# MB1297_MCU1.net
KiCad netlist of a schematic drawn in Altium Designer
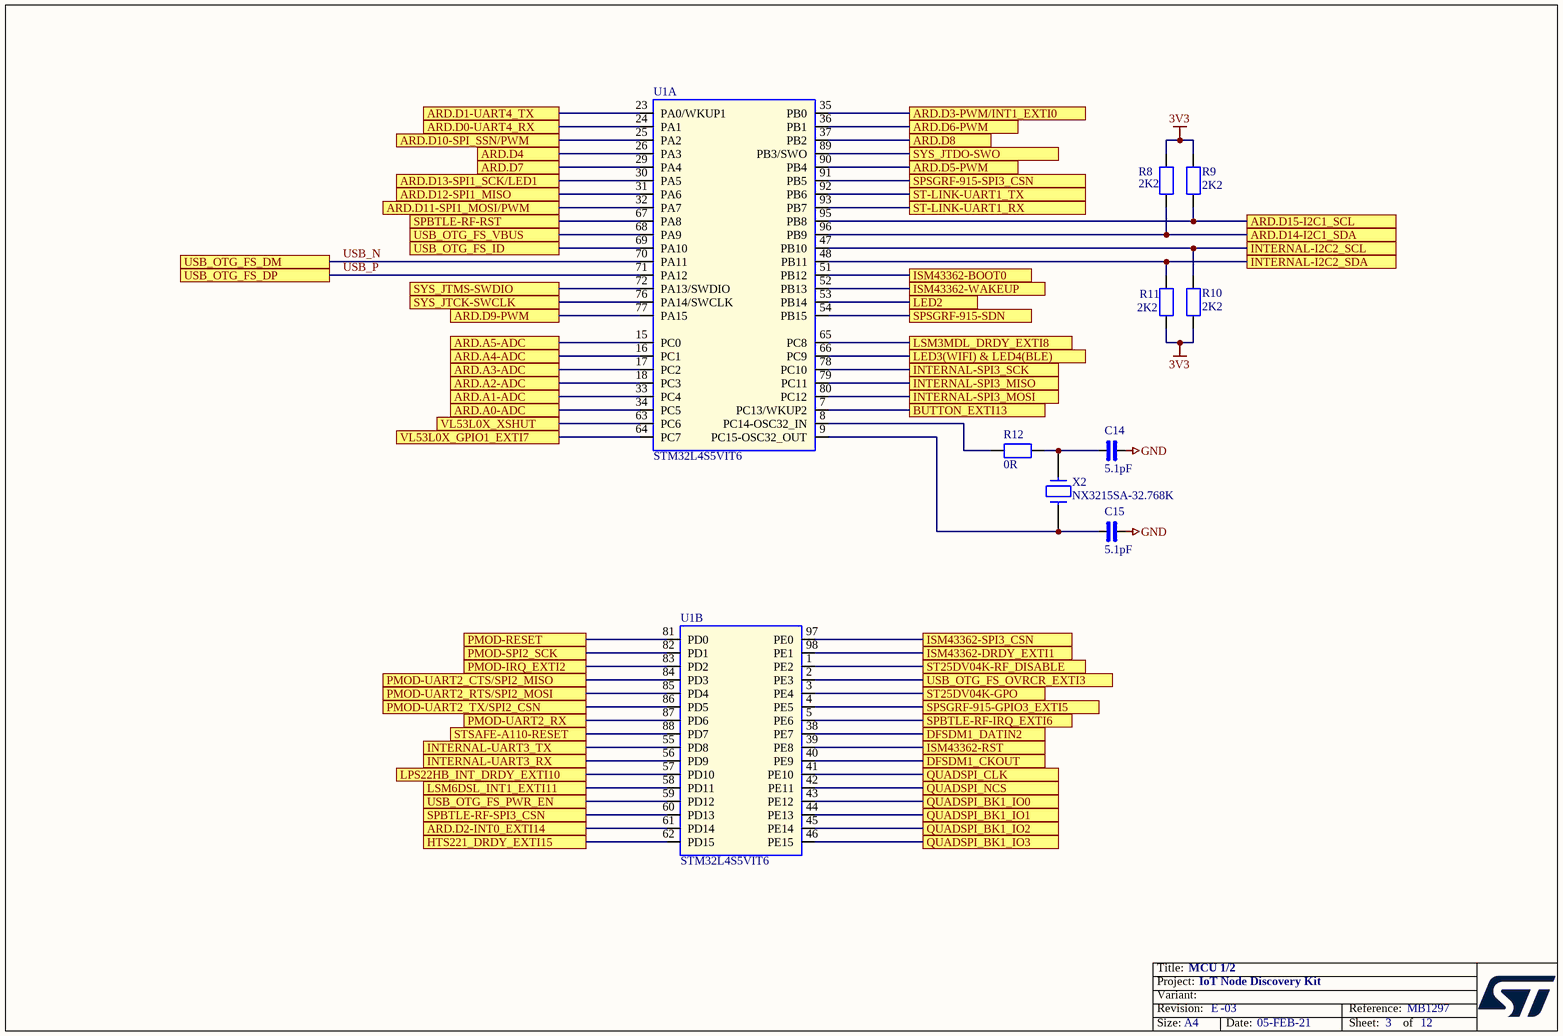
[diagram p0: MB1297_MCU1.SchDoc]

(export (version "E")
  (design (tool "Eeschema 10.0.6"))
  (components
    (comp (ref "C14")
      (value "5.1pF")
      (footprint "0402")
      (description "Capacitor_not polarized")
      (libsource (lib "ST_Lib3D") (part "CAP_NPOL"))
    )
    (comp (ref "C15")
      (value "5.1pF")
      (footprint "0402")
      (description "Capacitor_not polarized")
      (libsource (lib "ST_Lib3D") (part "CAP_NPOL"))
    )
    (comp (ref "R8")
      (value "2K2")
      (footprint "0402")
      (description "Resistor")
      (libsource (lib "ST_Lib3D") (part "RES"))
    )
    (comp (ref "R9")
      (value "2K2")
      (footprint "0402")
      (description "Resistor")
      (libsource (lib "ST_Lib3D") (part "RES"))
    )
    (comp (ref "R10")
      (value "2K2")
      (footprint "0402")
      (description "Resistor")
      (libsource (lib "ST_Lib3D") (part "RES"))
    )
    (comp (ref "R11")
      (value "2K2")
      (footprint "0402")
      (description "Resistor")
      (libsource (lib "ST_Lib3D") (part "RES"))
    )
    (comp (ref "R12")
      (value "0R")
      (footprint "0402")
      (description "Resistor")
      (libsource (lib "ST_Lib3D") (part "RES"))
    )
    (comp (ref "U1")
      (value "STM32L4S5VIT6")
      (footprint "ST_Lib3D:LQFP100 14x14x1.6")
      (description "STM32L475VGTx")
      (libsource (lib "ST_Lib3D") (part "STM32L475VGTx"))
    )
    (comp (ref "X2")
      (value "NX3215SA-32.768K")
      (footprint "CRY_NX3215SA_2P")
      (description "Crystal 32.768kHz, 6pF, -+20PPM, R=50K, SMD")
      (libsource (lib "MCD_TEMP_PCH") (part "XTAL_32K_NX3215SA"))
    )
  )
  (nets
    (net (code "1") (name "/ARD.A0-ADC") (class "Default")
      (node (ref "U1") (pin "34") (pinfunction "PC5_34") (pintype "passive"))
    )
    (net (code "2") (name "/ARD.A1-ADC") (class "Default")
      (node (ref "U1") (pin "33") (pinfunction "PC4_33") (pintype "passive"))
    )
    (net (code "3") (name "/ARD.A2-ADC") (class "Default")
      (node (ref "U1") (pin "18") (pinfunction "PC3_18") (pintype "passive"))
    )
    (net (code "4") (name "/ARD.A3-ADC") (class "Default")
      (node (ref "U1") (pin "17") (pinfunction "PC2_17") (pintype "passive"))
    )
    (net (code "5") (name "/ARD.A4-ADC") (class "Default")
      (node (ref "U1") (pin "16") (pinfunction "PC1_16") (pintype "passive"))
    )
    (net (code "6") (name "/ARD.A5-ADC") (class "Default")
      (node (ref "U1") (pin "15") (pinfunction "PC0_15") (pintype "passive"))
    )
    (net (code "7") (name "/ARD.D0-UART4_RX") (class "Default")
      (node (ref "U1") (pin "24") (pinfunction "PA1_24") (pintype "passive"))
    )
    (net (code "8") (name "/ARD.D1-UART4_TX") (class "Default")
      (node (ref "U1") (pin "23") (pinfunction "PA0/WKUP1_23") (pintype "passive"))
    )
    (net (code "9") (name "/ARD.D2-INT0_EXTI14") (class "Default")
      (node (ref "U1") (pin "61") (pinfunction "PD14_61") (pintype "passive"))
    )
    (net (code "10") (name "/ARD.D3-PWM{slash}INT1_EXTI0") (class "Default")
      (node (ref "U1") (pin "35") (pinfunction "PB0_35") (pintype "passive"))
    )
    (net (code "11") (name "/ARD.D4") (class "Default")
      (node (ref "U1") (pin "26") (pinfunction "PA3_26") (pintype "passive"))
    )
    (net (code "12") (name "/ARD.D5-PWM") (class "Default")
      (node (ref "U1") (pin "90") (pinfunction "PB4_90") (pintype "passive"))
    )
    (net (code "13") (name "/ARD.D6-PWM") (class "Default")
      (node (ref "U1") (pin "36") (pinfunction "PB1_36") (pintype "passive"))
    )
    (net (code "14") (name "/ARD.D7") (class "Default")
      (node (ref "U1") (pin "29") (pinfunction "PA4_29") (pintype "passive"))
    )
    (net (code "15") (name "/ARD.D8") (class "Default")
      (node (ref "U1") (pin "37") (pinfunction "PB2_37") (pintype "passive"))
    )
    (net (code "16") (name "/ARD.D9-PWM") (class "Default")
      (node (ref "U1") (pin "77") (pinfunction "PA15_77") (pintype "passive"))
    )
    (net (code "17") (name "/ARD.D10-SPI_SSN{slash}PWM") (class "Default")
      (node (ref "U1") (pin "25") (pinfunction "PA2_25") (pintype "passive"))
    )
    (net (code "18") (name "/ARD.D11-SPI1_MOSI{slash}PWM") (class "Default")
      (node (ref "U1") (pin "32") (pinfunction "PA7_32") (pintype "passive"))
    )
    (net (code "19") (name "/ARD.D12-SPI1_MISO") (class "Default")
      (node (ref "U1") (pin "31") (pinfunction "PA6_31") (pintype "passive"))
    )
    (net (code "20") (name "/ARD.D13-SPI1_SCK{slash}LED1") (class "Default")
      (node (ref "U1") (pin "30") (pinfunction "PA5_30") (pintype "passive"))
    )
    (net (code "21") (name "/ARD.D14-I2C1_SDA") (class "Default")
      (node (ref "R8") (pin "2") (pinfunction "2_2") (pintype "passive"))
      (node (ref "U1") (pin "96") (pinfunction "PB9_96") (pintype "passive"))
    )
    (net (code "22") (name "/ARD.D15-I2C1_SCL") (class "Default")
      (node (ref "R9") (pin "2") (pinfunction "2_2") (pintype "passive"))
      (node (ref "U1") (pin "95") (pinfunction "PB8_95") (pintype "passive"))
    )
    (net (code "23") (name "/BUTTON_EXTI13") (class "Default")
      (node (ref "U1") (pin "7") (pinfunction "PC13/WKUP2_7") (pintype "passive"))
    )
    (net (code "24") (name "/DFSDM1_CKOUT") (class "Default")
      (node (ref "U1") (pin "40") (pinfunction "PE9_40") (pintype "passive"))
    )
    (net (code "25") (name "/DFSDM1_DATIN2") (class "Default")
      (node (ref "U1") (pin "38") (pinfunction "PE7_38") (pintype "passive"))
    )
    (net (code "26") (name "/HTS221_DRDY_EXTI15") (class "Default")
      (node (ref "U1") (pin "62") (pinfunction "PD15_62") (pintype "passive"))
    )
    (net (code "27") (name "/INTERNAL-I2C2_SCL") (class "Default")
      (node (ref "R10") (pin "2") (pinfunction "2_2") (pintype "passive"))
      (node (ref "U1") (pin "47") (pinfunction "PB10_47") (pintype "passive"))
    )
    (net (code "28") (name "/INTERNAL-I2C2_SDA") (class "Default")
      (node (ref "R11") (pin "2") (pinfunction "2_2") (pintype "passive"))
      (node (ref "U1") (pin "48") (pinfunction "PB11_48") (pintype "passive"))
    )
    (net (code "29") (name "/INTERNAL-SPI3_MISO") (class "Default")
      (node (ref "U1") (pin "79") (pinfunction "PC11_79") (pintype "passive"))
    )
    (net (code "30") (name "/INTERNAL-SPI3_MOSI") (class "Default")
      (node (ref "U1") (pin "80") (pinfunction "PC12_80") (pintype "passive"))
    )
    (net (code "31") (name "/INTERNAL-SPI3_SCK") (class "Default")
      (node (ref "U1") (pin "78") (pinfunction "PC10_78") (pintype "passive"))
    )
    (net (code "32") (name "/INTERNAL-UART3_RX") (class "Default")
      (node (ref "U1") (pin "56") (pinfunction "PD9_56") (pintype "passive"))
    )
    (net (code "33") (name "/INTERNAL-UART3_TX") (class "Default")
      (node (ref "U1") (pin "55") (pinfunction "PD8_55") (pintype "passive"))
    )
    (net (code "34") (name "/ISM43362-BOOT0") (class "Default")
      (node (ref "U1") (pin "51") (pinfunction "PB12_51") (pintype "passive"))
    )
    (net (code "35") (name "/ISM43362-DRDY_EXTI1") (class "Default")
      (node (ref "U1") (pin "98") (pinfunction "PE1_98") (pintype "passive"))
    )
    (net (code "36") (name "/ISM43362-RST") (class "Default")
      (node (ref "U1") (pin "39") (pinfunction "PE8_39") (pintype "passive"))
    )
    (net (code "37") (name "/ISM43362-SPI3_CSN") (class "Default")
      (node (ref "U1") (pin "97") (pinfunction "PE0_97") (pintype "passive"))
    )
    (net (code "38") (name "/ISM43362-WAKEUP") (class "Default")
      (node (ref "U1") (pin "52") (pinfunction "PB13_52") (pintype "passive"))
    )
    (net (code "39") (name "/LED2") (class "Default")
      (node (ref "U1") (pin "53") (pinfunction "PB14_53") (pintype "passive"))
    )
    (net (code "40") (name "/LED3(WIFI) & LED4(BLE)") (class "Default")
      (node (ref "U1") (pin "66") (pinfunction "PC9_66") (pintype "passive"))
    )
    (net (code "41") (name "/LPS22HB_INT_DRDY_EXTI10") (class "Default")
      (node (ref "U1") (pin "57") (pinfunction "PD10_57") (pintype "passive"))
    )
    (net (code "42") (name "/LSM3MDL_DRDY_EXTI8") (class "Default")
      (node (ref "U1") (pin "65") (pinfunction "PC8_65") (pintype "passive"))
    )
    (net (code "43") (name "/LSM6DSL_INT1_EXTI11") (class "Default")
      (node (ref "U1") (pin "58") (pinfunction "PD11_58") (pintype "passive"))
    )
    (net (code "44") (name "/PMOD-IRQ_EXTI2") (class "Default")
      (node (ref "U1") (pin "83") (pinfunction "PD2_83") (pintype "passive"))
    )
    (net (code "45") (name "/PMOD-RESET") (class "Default")
      (node (ref "U1") (pin "81") (pinfunction "PD0_81") (pintype "passive"))
    )
    (net (code "46") (name "/PMOD-SPI2_SCK") (class "Default")
      (node (ref "U1") (pin "82") (pinfunction "PD1_82") (pintype "passive"))
    )
    (net (code "47") (name "/PMOD-UART2_CTS{slash}SPI2_MISO") (class "Default")
      (node (ref "U1") (pin "84") (pinfunction "PD3_84") (pintype "passive"))
    )
    (net (code "48") (name "/PMOD-UART2_RTS{slash}SPI2_MOSI") (class "Default")
      (node (ref "U1") (pin "85") (pinfunction "PD4_85") (pintype "passive"))
    )
    (net (code "49") (name "/PMOD-UART2_RX") (class "Default")
      (node (ref "U1") (pin "87") (pinfunction "PD6_87") (pintype "passive"))
    )
    (net (code "50") (name "/PMOD-UART2_TX{slash}SPI2_CSN") (class "Default")
      (node (ref "U1") (pin "86") (pinfunction "PD5_86") (pintype "passive"))
    )
    (net (code "51") (name "/QUADSPI_BK1_IO0") (class "Default")
      (node (ref "U1") (pin "43") (pinfunction "PE12_43") (pintype "passive"))
    )
    (net (code "52") (name "/QUADSPI_BK1_IO1") (class "Default")
      (node (ref "U1") (pin "44") (pinfunction "PE13_44") (pintype "passive"))
    )
    (net (code "53") (name "/QUADSPI_BK1_IO2") (class "Default")
      (node (ref "U1") (pin "45") (pinfunction "PE14_45") (pintype "passive"))
    )
    (net (code "54") (name "/QUADSPI_BK1_IO3") (class "Default")
      (node (ref "U1") (pin "46") (pinfunction "PE15_46") (pintype "passive"))
    )
    (net (code "55") (name "/QUADSPI_CLK") (class "Default")
      (node (ref "U1") (pin "41") (pinfunction "PE10_41") (pintype "passive"))
    )
    (net (code "56") (name "/QUADSPI_NCS") (class "Default")
      (node (ref "U1") (pin "42") (pinfunction "PE11_42") (pintype "passive"))
    )
    (net (code "57") (name "/SPBTLE-RF-IRQ_EXTI6") (class "Default")
      (node (ref "U1") (pin "5") (pinfunction "PE6_5") (pintype "passive"))
    )
    (net (code "58") (name "/SPBTLE-RF-RST") (class "Default")
      (node (ref "U1") (pin "67") (pinfunction "PA8_67") (pintype "passive"))
    )
    (net (code "59") (name "/SPBTLE-RF-SPI3_CSN") (class "Default")
      (node (ref "U1") (pin "60") (pinfunction "PD13_60") (pintype "passive"))
    )
    (net (code "60") (name "/SPSGRF-915-GPIO3_EXTI5") (class "Default")
      (node (ref "U1") (pin "4") (pinfunction "PE5_4") (pintype "passive"))
    )
    (net (code "61") (name "/SPSGRF-915-SDN") (class "Default")
      (node (ref "U1") (pin "54") (pinfunction "PB15_54") (pintype "passive"))
    )
    (net (code "62") (name "/SPSGRF-915-SPI3_CSN") (class "Default")
      (node (ref "U1") (pin "91") (pinfunction "PB5_91") (pintype "passive"))
    )
    (net (code "63") (name "/ST-LINK-UART1_RX") (class "Default")
      (node (ref "U1") (pin "93") (pinfunction "PB7_93") (pintype "passive"))
    )
    (net (code "64") (name "/ST-LINK-UART1_TX") (class "Default")
      (node (ref "U1") (pin "92") (pinfunction "PB6_92") (pintype "passive"))
    )
    (net (code "65") (name "/ST25DV04K-GPO") (class "Default")
      (node (ref "U1") (pin "3") (pinfunction "PE4_3") (pintype "passive"))
    )
    (net (code "66") (name "/ST25DV04K-RF_DISABLE") (class "Default")
      (node (ref "U1") (pin "1") (pinfunction "PE2_1") (pintype "passive"))
    )
    (net (code "67") (name "/STSAFE-A110-RESET") (class "Default")
      (node (ref "U1") (pin "88") (pinfunction "PD7_88") (pintype "passive"))
    )
    (net (code "68") (name "/SYS_JTCK-SWCLK") (class "Default")
      (node (ref "U1") (pin "76") (pinfunction "PA14/SWCLK_76") (pintype "passive"))
    )
    (net (code "69") (name "/SYS_JTDO-SWO") (class "Default")
      (node (ref "U1") (pin "89") (pinfunction "PB3/SWO_89") (pintype "passive"))
    )
    (net (code "70") (name "/SYS_JTMS-SWDIO") (class "Default")
      (node (ref "U1") (pin "72") (pinfunction "PA13/SWDIO_72") (pintype "passive"))
    )
    (net (code "71") (name "/USB_N") (class "Default")
      (node (ref "U1") (pin "70") (pinfunction "PA11_70") (pintype "passive"))
    )
    (net (code "72") (name "/USB_OTG_FS_ID") (class "Default")
      (node (ref "U1") (pin "69") (pinfunction "PA10_69") (pintype "passive"))
    )
    (net (code "73") (name "/USB_OTG_FS_OVRCR_EXTI3") (class "Default")
      (node (ref "U1") (pin "2") (pinfunction "PE3_2") (pintype "passive"))
    )
    (net (code "74") (name "/USB_OTG_FS_PWR_EN") (class "Default")
      (node (ref "U1") (pin "59") (pinfunction "PD12_59") (pintype "passive"))
    )
    (net (code "75") (name "/USB_OTG_FS_VBUS") (class "Default")
      (node (ref "U1") (pin "68") (pinfunction "PA9_68") (pintype "passive"))
    )
    (net (code "76") (name "/USB_P") (class "Default")
      (node (ref "U1") (pin "71") (pinfunction "PA12_71") (pintype "passive"))
    )
    (net (code "77") (name "/VL53L0X_GPIO1_EXTI7") (class "Default")
      (node (ref "U1") (pin "64") (pinfunction "PC7_64") (pintype "passive"))
    )
    (net (code "78") (name "/VL53L0X_XSHUT") (class "Default")
      (node (ref "U1") (pin "63") (pinfunction "PC6_63") (pintype "passive"))
    )
    (net (code "79") (name "3V3") (class "Default")
      (node (ref "R10") (pin "1") (pinfunction "1_1") (pintype "passive"))
      (node (ref "R11") (pin "1") (pinfunction "1_1") (pintype "passive"))
      (node (ref "R8") (pin "1") (pinfunction "1_1") (pintype "passive"))
      (node (ref "R9") (pin "1") (pinfunction "1_1") (pintype "passive"))
    )
    (net (code "80") (name "GND") (class "Default")
      (node (ref "C14") (pin "2") (pinfunction "2_2") (pintype "passive"))
      (node (ref "C15") (pin "2") (pinfunction "2_2") (pintype "passive"))
    )
    (net (code "81") (name "Net-(C14-Pad1)") (class "Default")
      (node (ref "C14") (pin "1") (pinfunction "1_1") (pintype "passive"))
      (node (ref "R12") (pin "2") (pinfunction "2_2") (pintype "passive"))
      (node (ref "X2") (pin "1") (pinfunction "1_1") (pintype "passive"))
    )
    (net (code "82") (name "Net-(U1A-PC14-OSC32_IN)") (class "Default")
      (node (ref "R12") (pin "1") (pinfunction "1_1") (pintype "passive"))
      (node (ref "U1") (pin "8") (pinfunction "PC14-OSC32_IN_8") (pintype "passive"))
    )
    (net (code "83") (name "Net-(U1A-PC15-OSC32_OUT)") (class "Default")
      (node (ref "C15") (pin "1") (pinfunction "1_1") (pintype "passive"))
      (node (ref "U1") (pin "9") (pinfunction "PC15-OSC32_OUT_9") (pintype "passive"))
      (node (ref "X2") (pin "2") (pinfunction "2_2") (pintype "passive"))
    )
  )
)
